# SHIELD_STM32F426ZI.net
KiCad netlist of a schematic drawn in EAGLE
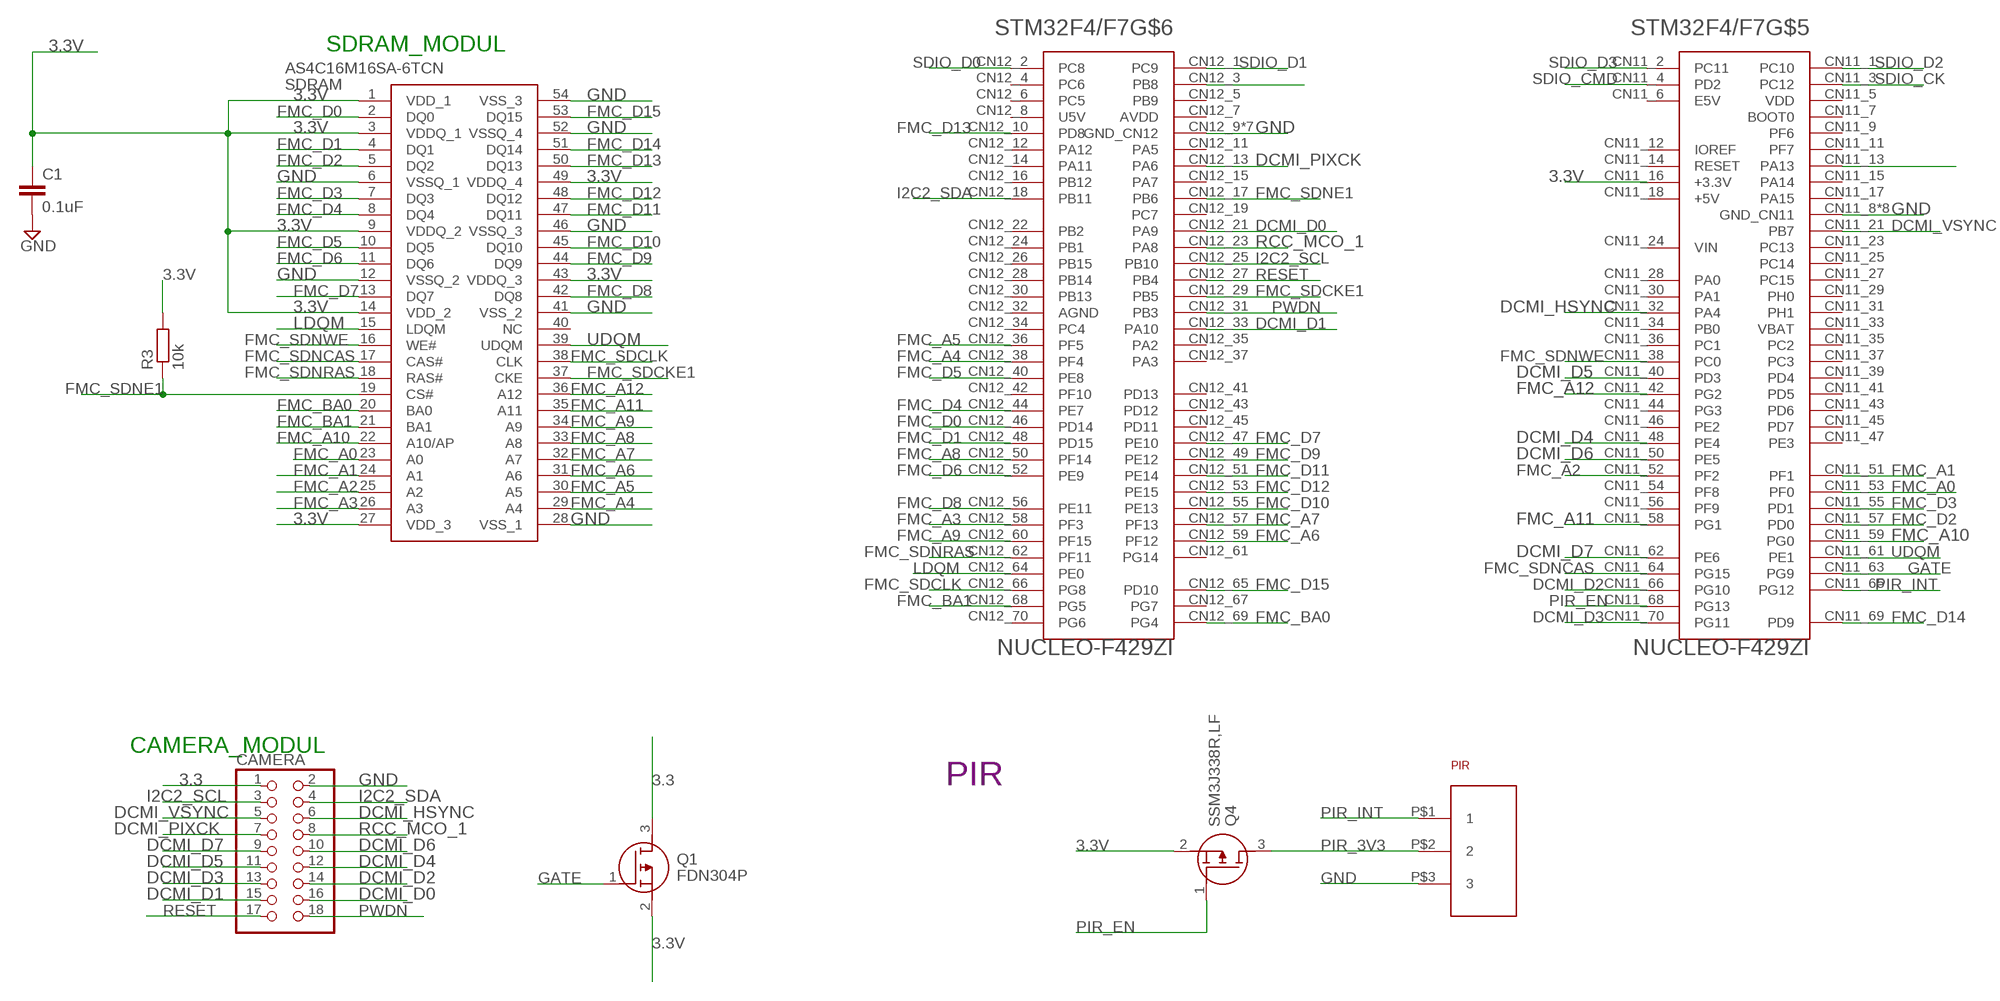
[diagram p0: schematic, sheet 1]
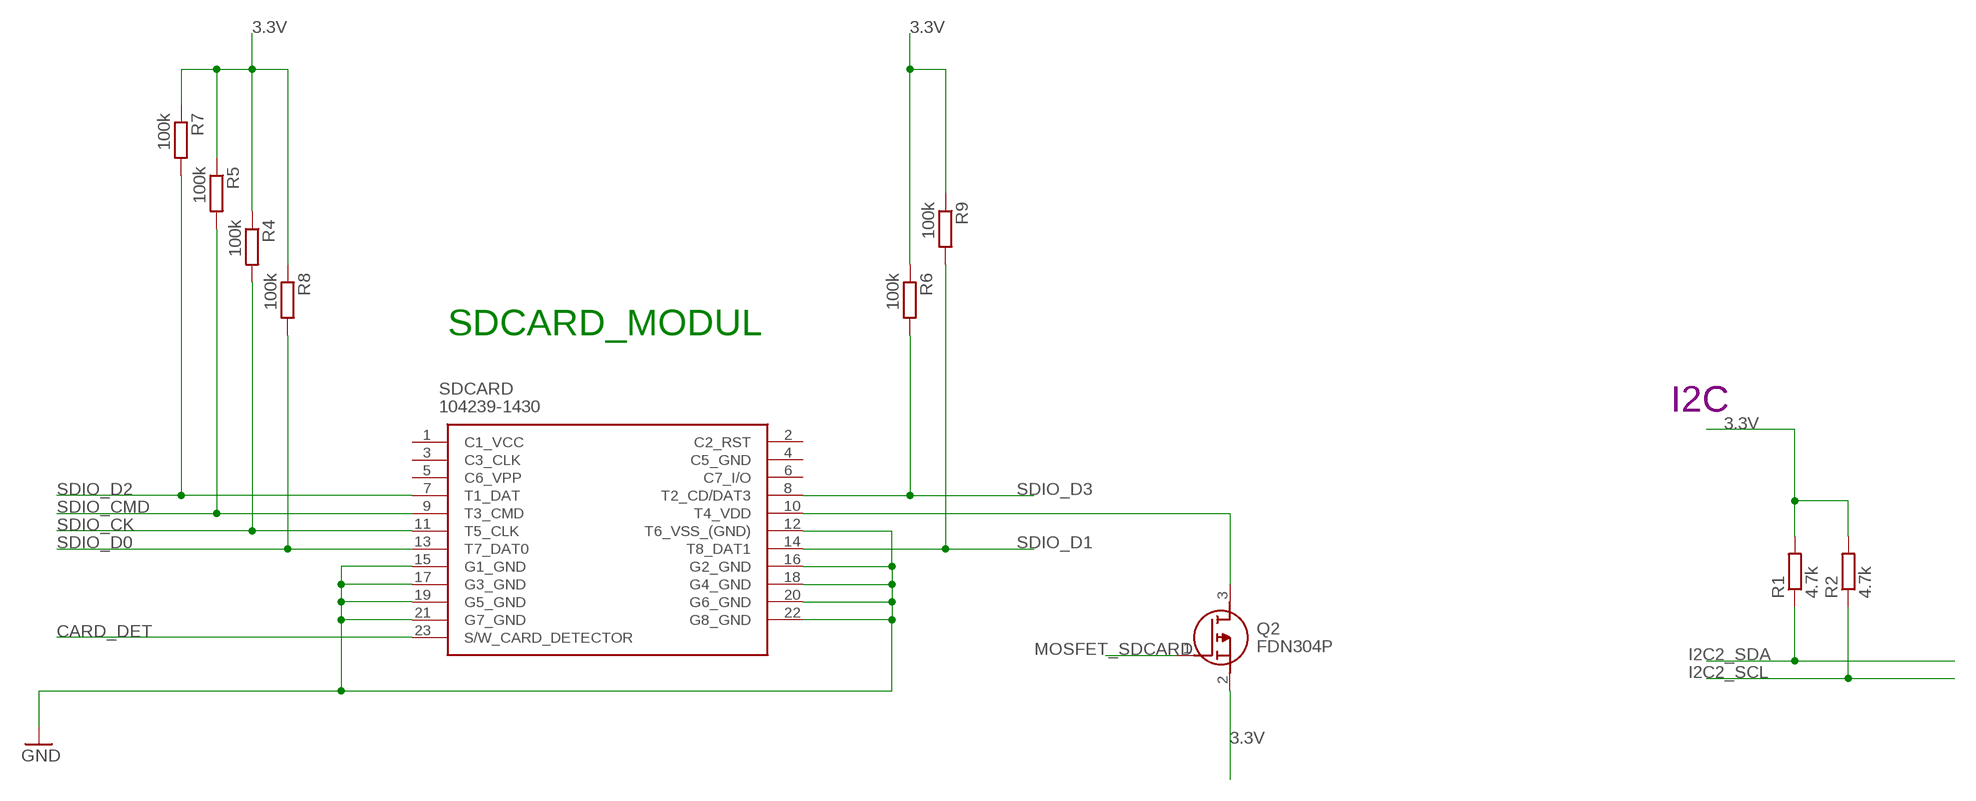
[diagram p1: schematic, sheet 2]

(export (version "E")
  (design (tool "Eeschema 10.0.6"))
  (components
    (comp (ref "C1")
      (value "0.1uF")
      (footprint "eagle-import:C0402K")
      (libsource (lib "eagle-import") (part "C-EUC0402K"))
    )
    (comp (ref "CAMERA")
      (value "0")
      (footprint "eagle-import:2X09")
      (libsource (lib "eagle-import") (part "PINHD-2X9"))
    )
    (comp (ref "PIR")
      (value "SENBA_PIR_3PIN")
      (footprint "eagle-import:SENBA_PIR")
      (libsource (lib "eagle-import") (part "SENBA_PIR_3PIN"))
    )
    (comp (ref "Q1")
      (value "FDN304P")
      (footprint "eagle-import:SOT95P237X112-3N")
      (fields (field (name "MOUSER_PART_NUMBER") "512-FDN304P"))
      (libsource (lib "eagle-import") (part "FDN304P"))
    )
    (comp (ref "Q4")
      (value "SSM3J338R,LF")
      (footprint "eagle-import:SSM3J332RLFT")
      (fields (field (name "MOUSER_PART_NUMBER") "757-SSM3J338RLF"))
      (libsource (lib "eagle-import") (part "SSM3J338R,LF"))
    )
    (comp (ref "R3")
      (value "10k")
      (footprint "eagle-import:C0402K")
      (libsource (lib "eagle-import") (part "R_0402WEB_0402"))
    )
    (comp (ref "SDRAM")
      (value "AS4C16M16SA-6TCN")
      (footprint "eagle-import:SOP80P1176X120-54N")
      (fields (field (name "MOUSER_PART_NUMBER") "913-4C16M16SA-6TCN"))
      (libsource (lib "eagle-import") (part "AS4C16M16SA-6TCN"))
    )
    (comp (ref "STM32F4/F7")
      (value "NUCLEO-F429ZI")
      (footprint "eagle-import:MODULE_NUCLEO-F429ZI")
      (fields (field (name "MF") "STMicroelectronics"))
      (libsource (lib "eagle-import") (part "NUCLEO-F429ZI"))
    )
    (comp (ref "Q2")
      (value "FDN304P")
      (footprint "eagle-import:SOT95P237X112-3N")
      (fields (field (name "MOUSER_PART_NUMBER") "512-FDN304P"))
      (libsource (lib "eagle-import") (part "FDN304P"))
    )
    (comp (ref "R1")
      (value "4.7k")
      (footprint "eagle-import:C0402K")
      (libsource (lib "eagle-import") (part "R_0402WEB_0402"))
    )
    (comp (ref "R2")
      (value "4.7k")
      (footprint "eagle-import:C0402K")
      (libsource (lib "eagle-import") (part "R_0402WEB_0402"))
    )
    (comp (ref "R4")
      (value "100k")
      (footprint "eagle-import:R0402")
      (libsource (lib "eagle-import") (part "R-EU_R0402"))
    )
    (comp (ref "R5")
      (value "100k")
      (footprint "eagle-import:R0402")
      (libsource (lib "eagle-import") (part "R-EU_R0402"))
    )
    (comp (ref "R6")
      (value "100k")
      (footprint "eagle-import:R0402")
      (libsource (lib "eagle-import") (part "R-EU_R0402"))
    )
    (comp (ref "R7")
      (value "100k")
      (footprint "eagle-import:R0402")
      (libsource (lib "eagle-import") (part "R-EU_R0402"))
    )
    (comp (ref "R8")
      (value "100k")
      (footprint "eagle-import:R0402")
      (libsource (lib "eagle-import") (part "R-EU_R0402"))
    )
    (comp (ref "R9")
      (value "100k")
      (footprint "eagle-import:R0402")
      (libsource (lib "eagle-import") (part "R-EU_R0402"))
    )
    (comp (ref "SDCARD")
      (value "104239-1430")
      (footprint "eagle-import:1042391430")
      (fields (field (name "MOUSER_PART_NUMBER") "538-104239-1430"))
      (libsource (lib "eagle-import") (part "104239-1430"))
    )
  )
  (nets
    (net (code "1") (name "3.3") (class "Default")
      (node (ref "CAMERA") (pin "1") (pinfunction "1_1") (pintype "passive"))
      (node (ref "Q1") (pin "3") (pinfunction "D_3") (pintype "bidirectional"))
    )
    (net (code "2") (name "3.3V") (class "Default")
      (node (ref "C1") (pin "1") (pinfunction "1_1") (pintype "passive"))
      (node (ref "Q1") (pin "2") (pinfunction "S_2") (pintype "bidirectional"))
      (node (ref "Q2") (pin "2") (pinfunction "S_2") (pintype "bidirectional"))
      (node (ref "Q4") (pin "2") (pinfunction "S_2") (pintype "bidirectional"))
      (node (ref "R1") (pin "2") (pinfunction "2_2") (pintype "passive"))
      (node (ref "R2") (pin "2") (pinfunction "2_2") (pintype "passive"))
      (node (ref "R3") (pin "2") (pinfunction "2_2") (pintype "passive"))
      (node (ref "R4") (pin "1") (pinfunction "1_1") (pintype "passive"))
      (node (ref "R5") (pin "1") (pinfunction "1_1") (pintype "passive"))
      (node (ref "R6") (pin "1") (pinfunction "1_1") (pintype "passive"))
      (node (ref "R7") (pin "1") (pinfunction "1_1") (pintype "passive"))
      (node (ref "R8") (pin "1") (pinfunction "1_1") (pintype "passive"))
      (node (ref "R9") (pin "1") (pinfunction "1_1") (pintype "passive"))
      (node (ref "SDRAM") (pin "1") (pinfunction "VDD_1_1") (pintype "bidirectional"))
      (node (ref "SDRAM") (pin "14") (pinfunction "VDD_2_14") (pintype "bidirectional"))
      (node (ref "SDRAM") (pin "27") (pinfunction "VDD_3_27") (pintype "bidirectional"))
      (node (ref "SDRAM") (pin "3") (pinfunction "VDDQ_1_3") (pintype "bidirectional"))
      (node (ref "SDRAM") (pin "43") (pinfunction "VDDQ_3_43") (pintype "bidirectional"))
      (node (ref "SDRAM") (pin "49") (pinfunction "VDDQ_4_49") (pintype "bidirectional"))
      (node (ref "SDRAM") (pin "9") (pinfunction "VDDQ_2_9") (pintype "bidirectional"))
      (node (ref "STM32F4/F7") (pin "CN11_16") (pinfunction "+3.3V_CN11_16") (pintype "passive"))
    )
    (net (code "3") (name "CARD_DET") (class "Default")
      (node (ref "SDCARD") (pin "23") (pinfunction "S/W_CARD_DETECTOR_23") (pintype "bidirectional"))
      (node (ref "STM32F4/F7") (pin "CN12_3") (pinfunction "PB8_CN12_3") (pintype "passive"))
    )
    (net (code "4") (name "DCMI_D0") (class "Default")
      (node (ref "CAMERA") (pin "16") (pinfunction "16_16") (pintype "passive"))
      (node (ref "STM32F4/F7") (pin "CN12_21") (pinfunction "PA9_CN12_21") (pintype "passive"))
    )
    (net (code "5") (name "DCMI_D1") (class "Default")
      (node (ref "CAMERA") (pin "15") (pinfunction "15_15") (pintype "passive"))
      (node (ref "STM32F4/F7") (pin "CN12_33") (pinfunction "PA10_CN12_33") (pintype "passive"))
    )
    (net (code "6") (name "DCMI_D2") (class "Default")
      (node (ref "CAMERA") (pin "14") (pinfunction "14_14") (pintype "passive"))
      (node (ref "STM32F4/F7") (pin "CN11_66") (pinfunction "PG10_CN11_66") (pintype "passive"))
    )
    (net (code "7") (name "DCMI_D3") (class "Default")
      (node (ref "CAMERA") (pin "13") (pinfunction "13_13") (pintype "passive"))
      (node (ref "STM32F4/F7") (pin "CN11_70") (pinfunction "PG11_CN11_70") (pintype "passive"))
    )
    (net (code "8") (name "DCMI_D4") (class "Default")
      (node (ref "CAMERA") (pin "12") (pinfunction "12_12") (pintype "passive"))
      (node (ref "STM32F4/F7") (pin "CN11_48") (pinfunction "PE4_CN11_48") (pintype "passive"))
    )
    (net (code "9") (name "DCMI_D5") (class "Default")
      (node (ref "CAMERA") (pin "11") (pinfunction "11_11") (pintype "passive"))
      (node (ref "STM32F4/F7") (pin "CN11_40") (pinfunction "PD3_CN11_40") (pintype "passive"))
    )
    (net (code "10") (name "DCMI_D6") (class "Default")
      (node (ref "CAMERA") (pin "10") (pinfunction "10_10") (pintype "passive"))
      (node (ref "STM32F4/F7") (pin "CN11_50") (pinfunction "PE5_CN11_50") (pintype "passive"))
    )
    (net (code "11") (name "DCMI_D7") (class "Default")
      (node (ref "CAMERA") (pin "9") (pinfunction "9_9") (pintype "passive"))
      (node (ref "STM32F4/F7") (pin "CN11_62") (pinfunction "PE6_CN11_62") (pintype "passive"))
    )
    (net (code "12") (name "DCMI_HSYNC") (class "Default")
      (node (ref "CAMERA") (pin "6") (pinfunction "6_6") (pintype "passive"))
      (node (ref "STM32F4/F7") (pin "CN11_32") (pinfunction "PA4_CN11_32") (pintype "passive"))
    )
    (net (code "13") (name "DCMI_PIXCK") (class "Default")
      (node (ref "CAMERA") (pin "7") (pinfunction "7_7") (pintype "passive"))
      (node (ref "STM32F4/F7") (pin "CN12_13") (pinfunction "PA6_CN12_13") (pintype "passive"))
    )
    (net (code "14") (name "DCMI_VSYNC") (class "Default")
      (node (ref "CAMERA") (pin "5") (pinfunction "5_5") (pintype "passive"))
      (node (ref "STM32F4/F7") (pin "CN11_21") (pinfunction "PB7_CN11_21") (pintype "passive"))
    )
    (net (code "15") (name "FMC_A0") (class "Default")
      (node (ref "SDRAM") (pin "23") (pinfunction "A0_23") (pintype "bidirectional"))
      (node (ref "STM32F4/F7") (pin "CN11_53") (pinfunction "PF0_CN11_53") (pintype "passive"))
    )
    (net (code "16") (name "FMC_A1") (class "Default")
      (node (ref "SDRAM") (pin "24") (pinfunction "A1_24") (pintype "bidirectional"))
      (node (ref "STM32F4/F7") (pin "CN11_51") (pinfunction "PF1_CN11_51") (pintype "passive"))
    )
    (net (code "17") (name "FMC_A2") (class "Default")
      (node (ref "SDRAM") (pin "25") (pinfunction "A2_25") (pintype "bidirectional"))
      (node (ref "STM32F4/F7") (pin "CN11_52") (pinfunction "PF2_CN11_52") (pintype "passive"))
    )
    (net (code "18") (name "FMC_A3") (class "Default")
      (node (ref "SDRAM") (pin "26") (pinfunction "A3_26") (pintype "bidirectional"))
      (node (ref "STM32F4/F7") (pin "CN12_58") (pinfunction "PF3_CN12_58") (pintype "passive"))
    )
    (net (code "19") (name "FMC_A4") (class "Default")
      (node (ref "SDRAM") (pin "29") (pinfunction "A4_29") (pintype "bidirectional"))
      (node (ref "STM32F4/F7") (pin "CN12_38") (pinfunction "PF4_CN12_38") (pintype "passive"))
    )
    (net (code "20") (name "FMC_A5") (class "Default")
      (node (ref "SDRAM") (pin "30") (pinfunction "A5_30") (pintype "bidirectional"))
      (node (ref "STM32F4/F7") (pin "CN12_36") (pinfunction "PF5_CN12_36") (pintype "passive"))
    )
    (net (code "21") (name "FMC_A6") (class "Default")
      (node (ref "SDRAM") (pin "31") (pinfunction "A6_31") (pintype "bidirectional"))
      (node (ref "STM32F4/F7") (pin "CN12_59") (pinfunction "PF12_CN12_59") (pintype "passive"))
    )
    (net (code "22") (name "FMC_A7") (class "Default")
      (node (ref "SDRAM") (pin "32") (pinfunction "A7_32") (pintype "bidirectional"))
      (node (ref "STM32F4/F7") (pin "CN12_57") (pinfunction "PF13_CN12_57") (pintype "passive"))
    )
    (net (code "23") (name "FMC_A8") (class "Default")
      (node (ref "SDRAM") (pin "33") (pinfunction "A8_33") (pintype "bidirectional"))
      (node (ref "STM32F4/F7") (pin "CN12_50") (pinfunction "PF14_CN12_50") (pintype "passive"))
    )
    (net (code "24") (name "FMC_A9") (class "Default")
      (node (ref "SDRAM") (pin "34") (pinfunction "A9_34") (pintype "bidirectional"))
      (node (ref "STM32F4/F7") (pin "CN12_60") (pinfunction "PF15_CN12_60") (pintype "passive"))
    )
    (net (code "25") (name "FMC_A10") (class "Default")
      (node (ref "SDRAM") (pin "22") (pinfunction "A10/AP_22") (pintype "bidirectional"))
      (node (ref "STM32F4/F7") (pin "CN11_59") (pinfunction "PG0_CN11_59") (pintype "passive"))
    )
    (net (code "26") (name "FMC_A11") (class "Default")
      (node (ref "SDRAM") (pin "35") (pinfunction "A11_35") (pintype "bidirectional"))
      (node (ref "STM32F4/F7") (pin "CN11_58") (pinfunction "PG1_CN11_58") (pintype "passive"))
    )
    (net (code "27") (name "FMC_A12") (class "Default")
      (node (ref "SDRAM") (pin "36") (pinfunction "A12_36") (pintype "bidirectional"))
      (node (ref "STM32F4/F7") (pin "CN11_42") (pinfunction "PG2_CN11_42") (pintype "passive"))
    )
    (net (code "28") (name "FMC_BA0") (class "Default")
      (node (ref "SDRAM") (pin "20") (pinfunction "BA0_20") (pintype "bidirectional"))
      (node (ref "STM32F4/F7") (pin "CN12_69") (pinfunction "PG4_CN12_69") (pintype "passive"))
    )
    (net (code "29") (name "FMC_BA1") (class "Default")
      (node (ref "SDRAM") (pin "21") (pinfunction "BA1_21") (pintype "bidirectional"))
      (node (ref "STM32F4/F7") (pin "CN12_68") (pinfunction "PG5_CN12_68") (pintype "passive"))
    )
    (net (code "30") (name "FMC_D0") (class "Default")
      (node (ref "SDRAM") (pin "2") (pinfunction "DQ0_2") (pintype "bidirectional"))
      (node (ref "STM32F4/F7") (pin "CN12_46") (pinfunction "PD14_CN12_46") (pintype "passive"))
    )
    (net (code "31") (name "FMC_D1") (class "Default")
      (node (ref "SDRAM") (pin "4") (pinfunction "DQ1_4") (pintype "bidirectional"))
      (node (ref "STM32F4/F7") (pin "CN12_48") (pinfunction "PD15_CN12_48") (pintype "passive"))
    )
    (net (code "32") (name "FMC_D2") (class "Default")
      (node (ref "SDRAM") (pin "5") (pinfunction "DQ2_5") (pintype "bidirectional"))
      (node (ref "STM32F4/F7") (pin "CN11_57") (pinfunction "PD0_CN11_57") (pintype "passive"))
    )
    (net (code "33") (name "FMC_D3") (class "Default")
      (node (ref "SDRAM") (pin "7") (pinfunction "DQ3_7") (pintype "bidirectional"))
      (node (ref "STM32F4/F7") (pin "CN11_55") (pinfunction "PD1_CN11_55") (pintype "passive"))
    )
    (net (code "34") (name "FMC_D4") (class "Default")
      (node (ref "SDRAM") (pin "8") (pinfunction "DQ4_8") (pintype "bidirectional"))
      (node (ref "STM32F4/F7") (pin "CN12_44") (pinfunction "PE7_CN12_44") (pintype "passive"))
    )
    (net (code "35") (name "FMC_D5") (class "Default")
      (node (ref "SDRAM") (pin "10") (pinfunction "DQ5_10") (pintype "bidirectional"))
      (node (ref "STM32F4/F7") (pin "CN12_40") (pinfunction "PE8_CN12_40") (pintype "passive"))
    )
    (net (code "36") (name "FMC_D6") (class "Default")
      (node (ref "SDRAM") (pin "11") (pinfunction "DQ6_11") (pintype "bidirectional"))
      (node (ref "STM32F4/F7") (pin "CN12_52") (pinfunction "PE9_CN12_52") (pintype "passive"))
    )
    (net (code "37") (name "FMC_D7") (class "Default")
      (node (ref "SDRAM") (pin "13") (pinfunction "DQ7_13") (pintype "bidirectional"))
      (node (ref "STM32F4/F7") (pin "CN12_47") (pinfunction "PE10_CN12_47") (pintype "passive"))
    )
    (net (code "38") (name "FMC_D8") (class "Default")
      (node (ref "SDRAM") (pin "42") (pinfunction "DQ8_42") (pintype "bidirectional"))
      (node (ref "STM32F4/F7") (pin "CN12_56") (pinfunction "PE11_CN12_56") (pintype "passive"))
    )
    (net (code "39") (name "FMC_D9") (class "Default")
      (node (ref "SDRAM") (pin "44") (pinfunction "DQ9_44") (pintype "bidirectional"))
      (node (ref "STM32F4/F7") (pin "CN12_49") (pinfunction "PE12_CN12_49") (pintype "passive"))
    )
    (net (code "40") (name "FMC_D10") (class "Default")
      (node (ref "SDRAM") (pin "45") (pinfunction "DQ10_45") (pintype "bidirectional"))
      (node (ref "STM32F4/F7") (pin "CN12_55") (pinfunction "PE13_CN12_55") (pintype "passive"))
    )
    (net (code "41") (name "FMC_D11") (class "Default")
      (node (ref "SDRAM") (pin "47") (pinfunction "DQ11_47") (pintype "bidirectional"))
      (node (ref "STM32F4/F7") (pin "CN12_51") (pinfunction "PE14_CN12_51") (pintype "passive"))
    )
    (net (code "42") (name "FMC_D12") (class "Default")
      (node (ref "SDRAM") (pin "48") (pinfunction "DQ12_48") (pintype "bidirectional"))
      (node (ref "STM32F4/F7") (pin "CN12_53") (pinfunction "PE15_CN12_53") (pintype "passive"))
    )
    (net (code "43") (name "FMC_D13") (class "Default")
      (node (ref "SDRAM") (pin "50") (pinfunction "DQ13_50") (pintype "bidirectional"))
      (node (ref "STM32F4/F7") (pin "CN12_10") (pinfunction "PD8_CN12_10") (pintype "passive"))
    )
    (net (code "44") (name "FMC_D14") (class "Default")
      (node (ref "SDRAM") (pin "51") (pinfunction "DQ14_51") (pintype "bidirectional"))
      (node (ref "STM32F4/F7") (pin "CN11_69") (pinfunction "PD9_CN11_69") (pintype "passive"))
    )
    (net (code "45") (name "FMC_D15") (class "Default")
      (node (ref "SDRAM") (pin "53") (pinfunction "DQ15_53") (pintype "bidirectional"))
      (node (ref "STM32F4/F7") (pin "CN12_65") (pinfunction "PD10_CN12_65") (pintype "passive"))
    )
    (net (code "46") (name "FMC_SDCKE1") (class "Default")
      (node (ref "SDRAM") (pin "37") (pinfunction "CKE_37") (pintype "bidirectional"))
      (node (ref "STM32F4/F7") (pin "CN12_29") (pinfunction "PB5_CN12_29") (pintype "passive"))
    )
    (net (code "47") (name "FMC_SDCLK") (class "Default")
      (node (ref "SDRAM") (pin "38") (pinfunction "CLK_38") (pintype "bidirectional"))
      (node (ref "STM32F4/F7") (pin "CN12_66") (pinfunction "PG8_CN12_66") (pintype "passive"))
    )
    (net (code "48") (name "FMC_SDNCAS") (class "Default")
      (node (ref "SDRAM") (pin "17") (pinfunction "CAS#_17") (pintype "bidirectional"))
      (node (ref "STM32F4/F7") (pin "CN11_64") (pinfunction "PG15_CN11_64") (pintype "passive"))
    )
    (net (code "49") (name "FMC_SDNE1") (class "Default")
      (node (ref "R3") (pin "1") (pinfunction "1_1") (pintype "passive"))
      (node (ref "SDRAM") (pin "19") (pinfunction "CS#_19") (pintype "bidirectional"))
      (node (ref "STM32F4/F7") (pin "CN12_17") (pinfunction "PB6_CN12_17") (pintype "passive"))
    )
    (net (code "50") (name "FMC_SDNRAS") (class "Default")
      (node (ref "SDRAM") (pin "18") (pinfunction "RAS#_18") (pintype "bidirectional"))
      (node (ref "STM32F4/F7") (pin "CN12_62") (pinfunction "PF11_CN12_62") (pintype "passive"))
    )
    (net (code "51") (name "FMC_SDNWE") (class "Default")
      (node (ref "SDRAM") (pin "16") (pinfunction "WE#_16") (pintype "bidirectional"))
      (node (ref "STM32F4/F7") (pin "CN11_38") (pinfunction "PC0_CN11_38") (pintype "passive"))
    )
    (net (code "52") (name "GATE") (class "Default")
      (node (ref "Q1") (pin "1") (pinfunction "G_1") (pintype "bidirectional"))
      (node (ref "STM32F4/F7") (pin "CN11_63") (pinfunction "PG9_CN11_63") (pintype "passive"))
    )
    (net (code "53") (name "GND") (class "Default")
      (node (ref "C1") (pin "2") (pinfunction "2_2") (pintype "passive"))
      (node (ref "CAMERA") (pin "2") (pinfunction "2_2") (pintype "passive"))
      (node (ref "PIR") (pin "P$3") (pinfunction "3_P$3") (pintype "bidirectional"))
      (node (ref "SDCARD") (pin "12") (pinfunction "T6_VSS_(GND)_12") (pintype "bidirectional"))
      (node (ref "SDCARD") (pin "15") (pinfunction "G1_GND_15") (pintype "bidirectional"))
      (node (ref "SDCARD") (pin "16") (pinfunction "G2_GND_16") (pintype "bidirectional"))
      (node (ref "SDCARD") (pin "17") (pinfunction "G3_GND_17") (pintype "bidirectional"))
      (node (ref "SDCARD") (pin "18") (pinfunction "G4_GND_18") (pintype "bidirectional"))
      (node (ref "SDCARD") (pin "19") (pinfunction "G5_GND_19") (pintype "bidirectional"))
      (node (ref "SDCARD") (pin "20") (pinfunction "G6_GND_20") (pintype "bidirectional"))
      (node (ref "SDCARD") (pin "21") (pinfunction "G7_GND_21") (pintype "bidirectional"))
      (node (ref "SDCARD") (pin "22") (pinfunction "G8_GND_22") (pintype "bidirectional"))
      (node (ref "SDRAM") (pin "12") (pinfunction "VSSQ_2_12") (pintype "bidirectional"))
      (node (ref "SDRAM") (pin "28") (pinfunction "VSS_1_28") (pintype "bidirectional"))
      (node (ref "SDRAM") (pin "41") (pinfunction "VSS_2_41") (pintype "bidirectional"))
      (node (ref "SDRAM") (pin "46") (pinfunction "VSSQ_3_46") (pintype "bidirectional"))
      (node (ref "SDRAM") (pin "52") (pinfunction "VSSQ_4_52") (pintype "bidirectional"))
      (node (ref "SDRAM") (pin "54") (pinfunction "VSS_3_54") (pintype "bidirectional"))
      (node (ref "SDRAM") (pin "6") (pinfunction "VSSQ_1_6") (pintype "bidirectional"))
      (node (ref "STM32F4/F7") (pin "CN11_19") (pinfunction "GND_CN11_CN11_19") (pintype "passive"))
      (node (ref "STM32F4/F7") (pin "CN11_20") (pinfunction "GND_CN11_CN11_20") (pintype "passive"))
      (node (ref "STM32F4/F7") (pin "CN11_22") (pinfunction "GND_CN11_CN11_22") (pintype "passive"))
      (node (ref "STM32F4/F7") (pin "CN11_49") (pinfunction "GND_CN11_CN11_49") (pintype "passive"))
      (node (ref "STM32F4/F7") (pin "CN11_60") (pinfunction "GND_CN11_CN11_60") (pintype "passive"))
      (node (ref "STM32F4/F7") (pin "CN11_71") (pinfunction "GND_CN11_CN11_71") (pintype "passive"))
      (node (ref "STM32F4/F7") (pin "CN11_72") (pinfunction "GND_CN11_CN11_72") (pintype "passive"))
      (node (ref "STM32F4/F7") (pin "CN11_8") (pinfunction "GND_CN11_CN11_8") (pintype "passive"))
      (node (ref "STM32F4/F7") (pin "CN12_20") (pinfunction "GND_CN12_CN12_20") (pintype "passive"))
      (node (ref "STM32F4/F7") (pin "CN12_39") (pinfunction "GND_CN12_CN12_39") (pintype "passive"))
      (node (ref "STM32F4/F7") (pin "CN12_54") (pinfunction "GND_CN12_CN12_54") (pintype "passive"))
      (node (ref "STM32F4/F7") (pin "CN12_63") (pinfunction "GND_CN12_CN12_63") (pintype "passive"))
      (node (ref "STM32F4/F7") (pin "CN12_71") (pinfunction "GND_CN12_CN12_71") (pintype "passive"))
      (node (ref "STM32F4/F7") (pin "CN12_72") (pinfunction "GND_CN12_CN12_72") (pintype "passive"))
      (node (ref "STM32F4/F7") (pin "CN12_9") (pinfunction "GND_CN12_CN12_9") (pintype "passive"))
    )
    (net (code "54") (name "I2C2_SCL") (class "Default")
      (node (ref "CAMERA") (pin "3") (pinfunction "3_3") (pintype "passive"))
      (node (ref "R2") (pin "1") (pinfunction "1_1") (pintype "passive"))
      (node (ref "STM32F4/F7") (pin "CN12_25") (pinfunction "PB10_CN12_25") (pintype "passive"))
    )
    (net (code "55") (name "I2C2_SDA") (class "Default")
      (node (ref "CAMERA") (pin "4") (pinfunction "4_4") (pintype "passive"))
      (node (ref "R1") (pin "1") (pinfunction "1_1") (pintype "passive"))
      (node (ref "STM32F4/F7") (pin "CN12_18") (pinfunction "PB11_CN12_18") (pintype "passive"))
    )
    (net (code "56") (name "LDQM") (class "Default")
      (node (ref "SDRAM") (pin "15") (pinfunction "LDQM_15") (pintype "bidirectional"))
      (node (ref "STM32F4/F7") (pin "CN12_64") (pinfunction "PE0_CN12_64") (pintype "passive"))
    )
    (net (code "57") (name "MOSFET_SDCARD") (class "Default")
      (node (ref "Q2") (pin "1") (pinfunction "G_1") (pintype "bidirectional"))
      (node (ref "STM32F4/F7") (pin "CN11_13") (pinfunction "PA13_CN11_13") (pintype "passive"))
    )
    (net (code "58") (name "Net-(Q2-D)") (class "Default")
      (node (ref "Q2") (pin "3") (pinfunction "D_3") (pintype "bidirectional"))
      (node (ref "SDCARD") (pin "10") (pinfunction "T4_VDD_10") (pintype "bidirectional"))
    )
    (net (code "59") (name "PIR_3V3") (class "Default")
      (node (ref "PIR") (pin "P$2") (pinfunction "2_P$2") (pintype "bidirectional"))
      (node (ref "Q4") (pin "3") (pinfunction "D_3") (pintype "bidirectional"))
    )
    (net (code "60") (name "PIR_EN") (class "Default")
      (node (ref "Q4") (pin "1") (pinfunction "G_1") (pintype "bidirectional"))
      (node (ref "STM32F4/F7") (pin "CN11_68") (pinfunction "PG13_CN11_68") (pintype "passive"))
    )
    (net (code "61") (name "PIR_INT") (class "Default")
      (node (ref "PIR") (pin "P$1") (pinfunction "1_P$1") (pintype "bidirectional"))
      (node (ref "STM32F4/F7") (pin "CN11_65") (pinfunction "PG12_CN11_65") (pintype "passive"))
    )
    (net (code "62") (name "PWDN") (class "Default")
      (node (ref "CAMERA") (pin "18") (pinfunction "18_18") (pintype "passive"))
      (node (ref "STM32F4/F7") (pin "CN12_31") (pinfunction "PB3_CN12_31") (pintype "passive"))
    )
    (net (code "63") (name "RCC_MCO_1") (class "Default")
      (node (ref "CAMERA") (pin "8") (pinfunction "8_8") (pintype "passive"))
      (node (ref "STM32F4/F7") (pin "CN12_23") (pinfunction "PA8_CN12_23") (pintype "passive"))
    )
    (net (code "64") (name "RESET") (class "Default")
      (node (ref "CAMERA") (pin "17") (pinfunction "17_17") (pintype "passive"))
      (node (ref "STM32F4/F7") (pin "CN12_27") (pinfunction "PB4_CN12_27") (pintype "passive"))
    )
    (net (code "65") (name "SDIO_CK") (class "Default")
      (node (ref "R4") (pin "2") (pinfunction "2_2") (pintype "passive"))
      (node (ref "SDCARD") (pin "11") (pinfunction "T5_CLK_11") (pintype "bidirectional"))
      (node (ref "STM32F4/F7") (pin "CN11_3") (pinfunction "PC12_CN11_3") (pintype "passive"))
    )
    (net (code "66") (name "SDIO_CMD") (class "Default")
      (node (ref "R5") (pin "2") (pinfunction "2_2") (pintype "passive"))
      (node (ref "SDCARD") (pin "9") (pinfunction "T3_CMD_9") (pintype "bidirectional"))
      (node (ref "STM32F4/F7") (pin "CN11_4") (pinfunction "PD2_CN11_4") (pintype "passive"))
    )
    (net (code "67") (name "SDIO_D0") (class "Default")
      (node (ref "R8") (pin "2") (pinfunction "2_2") (pintype "passive"))
      (node (ref "SDCARD") (pin "13") (pinfunction "T7_DAT0_13") (pintype "bidirectional"))
      (node (ref "STM32F4/F7") (pin "CN12_2") (pinfunction "PC8_CN12_2") (pintype "passive"))
    )
    (net (code "68") (name "SDIO_D1") (class "Default")
      (node (ref "R9") (pin "2") (pinfunction "2_2") (pintype "passive"))
      (node (ref "SDCARD") (pin "14") (pinfunction "T8_DAT1_14") (pintype "bidirectional"))
      (node (ref "STM32F4/F7") (pin "CN12_1") (pinfunction "PC9_CN12_1") (pintype "passive"))
    )
    (net (code "69") (name "SDIO_D2") (class "Default")
      (node (ref "R7") (pin "2") (pinfunction "2_2") (pintype "passive"))
      (node (ref "SDCARD") (pin "7") (pinfunction "T1_DAT_7") (pintype "bidirectional"))
      (node (ref "STM32F4/F7") (pin "CN11_1") (pinfunction "PC10_CN11_1") (pintype "passive"))
    )
    (net (code "70") (name "SDIO_D3") (class "Default")
      (node (ref "R6") (pin "2") (pinfunction "2_2") (pintype "passive"))
      (node (ref "SDCARD") (pin "8") (pinfunction "T2_CD/DAT3_8") (pintype "bidirectional"))
      (node (ref "STM32F4/F7") (pin "CN11_2") (pinfunction "PC11_CN11_2") (pintype "passive"))
    )
    (net (code "71") (name "UDQM") (class "Default")
      (node (ref "SDRAM") (pin "39") (pinfunction "UDQM_39") (pintype "bidirectional"))
      (node (ref "STM32F4/F7") (pin "CN11_61") (pinfunction "PE1_CN11_61") (pintype "passive"))
    )
    (net (code "72") (name "unconnected-(SDCARD-C1_VCC-Pad1)") (class "Default")
      (node (ref "SDCARD") (pin "1") (pinfunction "C1_VCC_1") (pintype "bidirectional"))
    )
    (net (code "73") (name "unconnected-(SDCARD-C2_RST-Pad2)") (class "Default")
      (node (ref "SDCARD") (pin "2") (pinfunction "C2_RST_2") (pintype "bidirectional"))
    )
    (net (code "74") (name "unconnected-(SDCARD-C3_CLK-Pad3)") (class "Default")
      (node (ref "SDCARD") (pin "3") (pinfunction "C3_CLK_3") (pintype "bidirectional"))
    )
    (net (code "75") (name "unconnected-(SDCARD-C5_GND-Pad4)") (class "Default")
      (node (ref "SDCARD") (pin "4") (pinfunction "C5_GND_4") (pintype "bidirectional"))
    )
    (net (code "76") (name "unconnected-(SDCARD-C6_VPP-Pad5)") (class "Default")
      (node (ref "SDCARD") (pin "5") (pinfunction "C6_VPP_5") (pintype "bidirectional"))
    )
    (net (code "77") (name "unconnected-(SDCARD-C7_I{slash}O-Pad6)") (class "Default")
      (node (ref "SDCARD") (pin "6") (pinfunction "C7_I/O_6") (pintype "bidirectional"))
    )
    (net (code "78") (name "unconnected-(SDRAM-NC-Pad40)") (class "Default")
      (node (ref "SDRAM") (pin "40") (pinfunction "NC_40") (pintype "no_connect"))
    )
    (net (code "79") (name "unconnected-(STM32F4/F7A-+5V-PadCN11_18)") (class "Default")
      (node (ref "STM32F4/F7") (pin "CN11_18") (pinfunction "+5V_CN11_18") (pintype "passive"))
    )
    (net (code "80") (name "unconnected-(STM32F4/F7A-BOOT0-PadCN11_7)") (class "Default")
      (node (ref "STM32F4/F7") (pin "CN11_7") (pinfunction "BOOT0_CN11_7") (pintype "passive"))
    )
    (net (code "81") (name "unconnected-(STM32F4/F7A-E5V-PadCN11_6)") (class "Default")
      (node (ref "STM32F4/F7") (pin "CN11_6") (pinfunction "E5V_CN11_6") (pintype "passive"))
    )
    (net (code "82") (name "unconnected-(STM32F4/F7A-IOREF-PadCN11_12)") (class "Default")
      (node (ref "STM32F4/F7") (pin "CN11_12") (pinfunction "IOREF_CN11_12") (pintype "passive"))
    )
    (net (code "83") (name "unconnected-(STM32F4/F7A-PA0-PadCN11_28)") (class "Default")
      (node (ref "STM32F4/F7") (pin "CN11_28") (pinfunction "PA0_CN11_28") (pintype "passive"))
    )
    (net (code "84") (name "unconnected-(STM32F4/F7A-PA1-PadCN11_30)") (class "Default")
      (node (ref "STM32F4/F7") (pin "CN11_30") (pinfunction "PA1_CN11_30") (pintype "passive"))
    )
    (net (code "85") (name "unconnected-(STM32F4/F7A-PA14-PadCN11_15)") (class "Default")
      (node (ref "STM32F4/F7") (pin "CN11_15") (pinfunction "PA14_CN11_15") (pintype "passive"))
    )
    (net (code "86") (name "unconnected-(STM32F4/F7A-PA15-PadCN11_17)") (class "Default")
      (node (ref "STM32F4/F7") (pin "CN11_17") (pinfunction "PA15_CN11_17") (pintype "passive"))
    )
    (net (code "87") (name "unconnected-(STM32F4/F7A-PB0-PadCN11_34)") (class "Default")
      (node (ref "STM32F4/F7") (pin "CN11_34") (pinfunction "PB0_CN11_34") (pintype "passive"))
    )
    (net (code "88") (name "unconnected-(STM32F4/F7A-PC1-PadCN11_36)") (class "Default")
      (node (ref "STM32F4/F7") (pin "CN11_36") (pinfunction "PC1_CN11_36") (pintype "passive"))
    )
    (net (code "89") (name "unconnected-(STM32F4/F7A-PC2-PadCN11_35)") (class "Default")
      (node (ref "STM32F4/F7") (pin "CN11_35") (pinfunction "PC2_CN11_35") (pintype "passive"))
    )
    (net (code "90") (name "unconnected-(STM32F4/F7A-PC3-PadCN11_37)") (class "Default")
      (node (ref "STM32F4/F7") (pin "CN11_37") (pinfunction "PC3_CN11_37") (pintype "passive"))
    )
    (net (code "91") (name "unconnected-(STM32F4/F7A-PC13-PadCN11_23)") (class "Default")
      (node (ref "STM32F4/F7") (pin "CN11_23") (pinfunction "PC13_CN11_23") (pintype "passive"))
    )
    (net (code "92") (name "unconnected-(STM32F4/F7A-PC14-PadCN11_25)") (class "Default")
      (node (ref "STM32F4/F7") (pin "CN11_25") (pinfunction "PC14_CN11_25") (pintype "passive"))
    )
    (net (code "93") (name "unconnected-(STM32F4/F7A-PC15-PadCN11_27)") (class "Default")
      (node (ref "STM32F4/F7") (pin "CN11_27") (pinfunction "PC15_CN11_27") (pintype "passive"))
    )
    (net (code "94") (name "unconnected-(STM32F4/F7A-PD4-PadCN11_39)") (class "Default")
      (node (ref "STM32F4/F7") (pin "CN11_39") (pinfunction "PD4_CN11_39") (pintype "passive"))
    )
    (net (code "95") (name "unconnected-(STM32F4/F7A-PD5-PadCN11_41)") (class "Default")
      (node (ref "STM32F4/F7") (pin "CN11_41") (pinfunction "PD5_CN11_41") (pintype "passive"))
    )
    (net (code "96") (name "unconnected-(STM32F4/F7A-PD6-PadCN11_43)") (class "Default")
      (node (ref "STM32F4/F7") (pin "CN11_43") (pinfunction "PD6_CN11_43") (pintype "passive"))
    )
    (net (code "97") (name "unconnected-(STM32F4/F7A-PD7-PadCN11_45)") (class "Default")
      (node (ref "STM32F4/F7") (pin "CN11_45") (pinfunction "PD7_CN11_45") (pintype "passive"))
    )
    (net (code "98") (name "unconnected-(STM32F4/F7A-PE2-PadCN11_46)") (class "Default")
      (node (ref "STM32F4/F7") (pin "CN11_46") (pinfunction "PE2_CN11_46") (pintype "passive"))
    )
    (net (code "99") (name "unconnected-(STM32F4/F7A-PE3-PadCN11_47)") (class "Default")
      (node (ref "STM32F4/F7") (pin "CN11_47") (pinfunction "PE3_CN11_47") (pintype "passive"))
    )
    (net (code "100") (name "unconnected-(STM32F4/F7A-PF6-PadCN11_9)") (class "Default")
      (node (ref "STM32F4/F7") (pin "CN11_9") (pinfunction "PF6_CN11_9") (pintype "passive"))
    )
    (net (code "101") (name "unconnected-(STM32F4/F7A-PF7-PadCN11_11)") (class "Default")
      (node (ref "STM32F4/F7") (pin "CN11_11") (pinfunction "PF7_CN11_11") (pintype "passive"))
    )
    (net (code "102") (name "unconnected-(STM32F4/F7A-PF8-PadCN11_54)") (class "Default")
      (node (ref "STM32F4/F7") (pin "CN11_54") (pinfunction "PF8_CN11_54") (pintype "passive"))
    )
    (net (code "103") (name "unconnected-(STM32F4/F7A-PF9-PadCN11_56)") (class "Default")
      (node (ref "STM32F4/F7") (pin "CN11_56") (pinfunction "PF9_CN11_56") (pintype "passive"))
    )
    (net (code "104") (name "unconnected-(STM32F4/F7A-PG3-PadCN11_44)") (class "Default")
      (node (ref "STM32F4/F7") (pin "CN11_44") (pinfunction "PG3_CN11_44") (pintype "passive"))
    )
    (net (code "105") (name "unconnected-(STM32F4/F7A-PH0-PadCN11_29)") (class "Default")
      (node (ref "STM32F4/F7") (pin "CN11_29") (pinfunction "PH0_CN11_29") (pintype "passive"))
    )
    (net (code "106") (name "unconnected-(STM32F4/F7A-PH1-PadCN11_31)") (class "Default")
      (node (ref "STM32F4/F7") (pin "CN11_31") (pinfunction "PH1_CN11_31") (pintype "passive"))
    )
    (net (code "107") (name "unconnected-(STM32F4/F7A-RESET-PadCN11_14)") (class "Default")
      (node (ref "STM32F4/F7") (pin "CN11_14") (pinfunction "RESET_CN11_14") (pintype "passive"))
    )
    (net (code "108") (name "unconnected-(STM32F4/F7A-VBAT-PadCN11_33)") (class "Default")
      (node (ref "STM32F4/F7") (pin "CN11_33") (pinfunction "VBAT_CN11_33") (pintype "passive"))
    )
    (net (code "109") (name "unconnected-(STM32F4/F7A-VDD-PadCN11_5)") (class "Default")
      (node (ref "STM32F4/F7") (pin "CN11_5") (pinfunction "VDD_CN11_5") (pintype "passive"))
    )
    (net (code "110") (name "unconnected-(STM32F4/F7A-VIN-PadCN11_24)") (class "Default")
      (node (ref "STM32F4/F7") (pin "CN11_24") (pinfunction "VIN_CN11_24") (pintype "passive"))
    )
    (net (code "111") (name "unconnected-(STM32F4/F7B-AGND-PadCN12_32)") (class "Default")
      (node (ref "STM32F4/F7") (pin "CN12_32") (pinfunction "AGND_CN12_32") (pintype "passive"))
    )
    (net (code "112") (name "unconnected-(STM32F4/F7B-AVDD-PadCN12_7)") (class "Default")
      (node (ref "STM32F4/F7") (pin "CN12_7") (pinfunction "AVDD_CN12_7") (pintype "passive"))
    )
    (net (code "113") (name "unconnected-(STM32F4/F7B-PA2-PadCN12_35)") (class "Default")
      (node (ref "STM32F4/F7") (pin "CN12_35") (pinfunction "PA2_CN12_35") (pintype "passive"))
    )
    (net (code "114") (name "unconnected-(STM32F4/F7B-PA3-PadCN12_37)") (class "Default")
      (node (ref "STM32F4/F7") (pin "CN12_37") (pinfunction "PA3_CN12_37") (pintype "passive"))
    )
    (net (code "115") (name "unconnected-(STM32F4/F7B-PA5-PadCN12_11)") (class "Default")
      (node (ref "STM32F4/F7") (pin "CN12_11") (pinfunction "PA5_CN12_11") (pintype "passive"))
    )
    (net (code "116") (name "unconnected-(STM32F4/F7B-PA7-PadCN12_15)") (class "Default")
      (node (ref "STM32F4/F7") (pin "CN12_15") (pinfunction "PA7_CN12_15") (pintype "passive"))
    )
    (net (code "117") (name "unconnected-(STM32F4/F7B-PA11-PadCN12_14)") (class "Default")
      (node (ref "STM32F4/F7") (pin "CN12_14") (pinfunction "PA11_CN12_14") (pintype "passive"))
    )
    (net (code "118") (name "unconnected-(STM32F4/F7B-PA12-PadCN12_12)") (class "Default")
      (node (ref "STM32F4/F7") (pin "CN12_12") (pinfunction "PA12_CN12_12") (pintype "passive"))
    )
    (net (code "119") (name "unconnected-(STM32F4/F7B-PB1-PadCN12_24)") (class "Default")
      (node (ref "STM32F4/F7") (pin "CN12_24") (pinfunction "PB1_CN12_24") (pintype "passive"))
    )
    (net (code "120") (name "unconnected-(STM32F4/F7B-PB2-PadCN12_22)") (class "Default")
      (node (ref "STM32F4/F7") (pin "CN12_22") (pinfunction "PB2_CN12_22") (pintype "passive"))
    )
    (net (code "121") (name "unconnected-(STM32F4/F7B-PB9-PadCN12_5)") (class "Default")
      (node (ref "STM32F4/F7") (pin "CN12_5") (pinfunction "PB9_CN12_5") (pintype "passive"))
    )
    (net (code "122") (name "unconnected-(STM32F4/F7B-PB12-PadCN12_16)") (class "Default")
      (node (ref "STM32F4/F7") (pin "CN12_16") (pinfunction "PB12_CN12_16") (pintype "passive"))
    )
    (net (code "123") (name "unconnected-(STM32F4/F7B-PB13-PadCN12_30)") (class "Default")
      (node (ref "STM32F4/F7") (pin "CN12_30") (pinfunction "PB13_CN12_30") (pintype "passive"))
    )
    (net (code "124") (name "unconnected-(STM32F4/F7B-PB14-PadCN12_28)") (class "Default")
      (node (ref "STM32F4/F7") (pin "CN12_28") (pinfunction "PB14_CN12_28") (pintype "passive"))
    )
    (net (code "125") (name "unconnected-(STM32F4/F7B-PB15-PadCN12_26)") (class "Default")
      (node (ref "STM32F4/F7") (pin "CN12_26") (pinfunction "PB15_CN12_26") (pintype "passive"))
    )
    (net (code "126") (name "unconnected-(STM32F4/F7B-PC4-PadCN12_34)") (class "Default")
      (node (ref "STM32F4/F7") (pin "CN12_34") (pinfunction "PC4_CN12_34") (pintype "passive"))
    )
    (net (code "127") (name "unconnected-(STM32F4/F7B-PC5-PadCN12_6)") (class "Default")
      (node (ref "STM32F4/F7") (pin "CN12_6") (pinfunction "PC5_CN12_6") (pintype "passive"))
    )
    (net (code "128") (name "unconnected-(STM32F4/F7B-PC6-PadCN12_4)") (class "Default")
      (node (ref "STM32F4/F7") (pin "CN12_4") (pinfunction "PC6_CN12_4") (pintype "passive"))
    )
    (net (code "129") (name "unconnected-(STM32F4/F7B-PC7-PadCN12_19)") (class "Default")
      (node (ref "STM32F4/F7") (pin "CN12_19") (pinfunction "PC7_CN12_19") (pintype "passive"))
    )
    (net (code "130") (name "unconnected-(STM32F4/F7B-PD11-PadCN12_45)") (class "Default")
      (node (ref "STM32F4/F7") (pin "CN12_45") (pinfunction "PD11_CN12_45") (pintype "passive"))
    )
    (net (code "131") (name "unconnected-(STM32F4/F7B-PD12-PadCN12_43)") (class "Default")
      (node (ref "STM32F4/F7") (pin "CN12_43") (pinfunction "PD12_CN12_43") (pintype "passive"))
    )
    (net (code "132") (name "unconnected-(STM32F4/F7B-PD13-PadCN12_41)") (class "Default")
      (node (ref "STM32F4/F7") (pin "CN12_41") (pinfunction "PD13_CN12_41") (pintype "passive"))
    )
    (net (code "133") (name "unconnected-(STM32F4/F7B-PF10-PadCN12_42)") (class "Default")
      (node (ref "STM32F4/F7") (pin "CN12_42") (pinfunction "PF10_CN12_42") (pintype "passive"))
    )
    (net (code "134") (name "unconnected-(STM32F4/F7B-PG6-PadCN12_70)") (class "Default")
      (node (ref "STM32F4/F7") (pin "CN12_70") (pinfunction "PG6_CN12_70") (pintype "passive"))
    )
    (net (code "135") (name "unconnected-(STM32F4/F7B-PG7-PadCN12_67)") (class "Default")
      (node (ref "STM32F4/F7") (pin "CN12_67") (pinfunction "PG7_CN12_67") (pintype "passive"))
    )
    (net (code "136") (name "unconnected-(STM32F4/F7B-PG14-PadCN12_61)") (class "Default")
      (node (ref "STM32F4/F7") (pin "CN12_61") (pinfunction "PG14_CN12_61") (pintype "passive"))
    )
    (net (code "137") (name "unconnected-(STM32F4/F7B-U5V-PadCN12_8)") (class "Default")
      (node (ref "STM32F4/F7") (pin "CN12_8") (pinfunction "U5V_CN12_8") (pintype "passive"))
    )
  )
)
